# RT1064_Interaction.net
KiCad netlist of a schematic drawn in Altium Designer
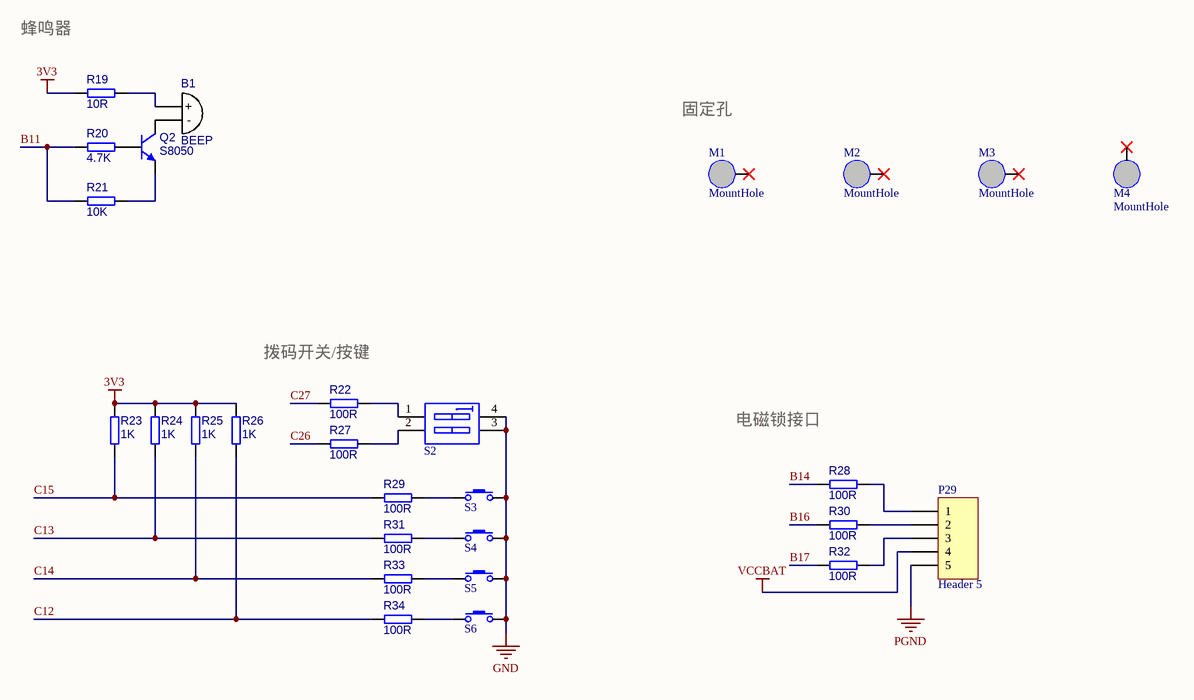
[diagram p0: RT1064_Interaction.SchDoc]

(export (version "E")
  (design (tool "Eeschema 10.0.6"))
  (components
    (comp (ref "B1")
      (value "BEEP")
      (footprint "BEEP 9x5.5mm")
      (description "蜂鸣器")
      (libsource (lib "RT1064_V1主板器件封装集成库") (part "BEEP"))
    )
    (comp (ref "M1")
      (value "MountHole")
      (footprint "M3-MountHole")
      (description "固定孔")
      (libsource (lib "RT1064_V1主板器件封装集成库") (part "MountHole"))
    )
    (comp (ref "M2")
      (value "MountHole")
      (footprint "M3-MountHole")
      (description "固定孔")
      (libsource (lib "RT1064_V1主板器件封装集成库") (part "MountHole"))
    )
    (comp (ref "M3")
      (value "MountHole")
      (footprint "M3-MountHole")
      (description "固定孔")
      (libsource (lib "RT1064_V1主板器件封装集成库") (part "MountHole"))
    )
    (comp (ref "M4")
      (value "MountHole")
      (footprint "M3-MountHole")
      (description "固定孔")
      (libsource (lib "RT1064_V1主板器件封装集成库") (part "MountHole"))
    )
    (comp (ref "P29")
      (value "Header 5")
      (footprint "HDR1X5")
      (description "Header, 5-Pin")
      (fields (field (name "PUBLISHER") "Altium Limited"))
      (libsource (lib "Miscellaneous Connectors") (part "Header 5"))
    )
    (comp (ref "Q2")
      (value "S8050")
      (footprint "SOT-23")
      (description "Discrete NPN Bipolar Transistor")
      (fields (field (name "PARTNUMBER") "S8050") (field (name "PUBLISHER") "Altium Limited"))
      (libsource (lib "RT1064_V1主板器件封装集成库") (part "NPN S8050"))
    )
    (comp (ref "R19")
      (value "10R")
      (footprint "RESC1608[0603]S-L")
      (description "贴片电阻")
      (fields (field (name "POWER") "1/8W") (field (name "TOLERANCE") "±1%"))
      (libsource (lib "RT1064_V1主板器件封装集成库") (part "Res-Chip"))
    )
    (comp (ref "R20")
      (value "4.7K")
      (footprint "RESC1608[0603]S-L")
      (description "贴片电阻")
      (fields (field (name "POWER") "1/8W") (field (name "TOLERANCE") "±1%"))
      (libsource (lib "RT1064_V1主板器件封装集成库") (part "Res-Chip"))
    )
    (comp (ref "R21")
      (value "10K")
      (footprint "RESC1608[0603]S-L")
      (description "贴片电阻")
      (fields (field (name "POWER") "1/8W") (field (name "TOLERANCE") "±1%"))
      (libsource (lib "RT1064_V1主板器件封装集成库") (part "Res-Chip"))
    )
    (comp (ref "R22")
      (value "100R")
      (footprint "RESC1608[0603]S-L")
      (description "贴片电阻")
      (fields (field (name "POWER") "1/8W") (field (name "TOLERANCE") "±1%"))
      (libsource (lib "RT1064_V1主板器件封装集成库") (part "Res-Chip"))
    )
    (comp (ref "R23")
      (value "1K")
      (footprint "RESC1608[0603]S-L")
      (description "贴片电阻")
      (fields (field (name "POWER") "1/8W") (field (name "TOLERANCE") "±1%"))
      (libsource (lib "RT1064_V1主板器件封装集成库") (part "Res-Chip"))
    )
    (comp (ref "R24")
      (value "1K")
      (footprint "RESC1608[0603]S-L")
      (description "贴片电阻")
      (fields (field (name "POWER") "1/8W") (field (name "TOLERANCE") "±1%"))
      (libsource (lib "RT1064_V1主板器件封装集成库") (part "Res-Chip"))
    )
    (comp (ref "R25")
      (value "1K")
      (footprint "RESC1608[0603]S-L")
      (description "贴片电阻")
      (fields (field (name "POWER") "1/8W") (field (name "TOLERANCE") "±1%"))
      (libsource (lib "RT1064_V1主板器件封装集成库") (part "Res-Chip"))
    )
    (comp (ref "R26")
      (value "1K")
      (footprint "RESC1608[0603]S-L")
      (description "贴片电阻")
      (fields (field (name "POWER") "1/8W") (field (name "TOLERANCE") "±1%"))
      (libsource (lib "RT1064_V1主板器件封装集成库") (part "Res-Chip"))
    )
    (comp (ref "R27")
      (value "100R")
      (footprint "RESC1608[0603]S-L")
      (description "贴片电阻")
      (fields (field (name "POWER") "1/8W") (field (name "TOLERANCE") "±1%"))
      (libsource (lib "RT1064_V1主板器件封装集成库") (part "Res-Chip"))
    )
    (comp (ref "R28")
      (value "100R")
      (footprint "RESC1608[0603]S-L")
      (description "贴片电阻")
      (fields (field (name "POWER") "1/8W") (field (name "TOLERANCE") "±1%"))
      (libsource (lib "RT1064_V1主板器件封装集成库") (part "Res-Chip"))
    )
    (comp (ref "R29")
      (value "100R")
      (footprint "RESC1608[0603]S-L")
      (description "贴片电阻")
      (fields (field (name "POWER") "1/8W") (field (name "TOLERANCE") "±1%"))
      (libsource (lib "RT1064_V1主板器件封装集成库") (part "Res-Chip"))
    )
    (comp (ref "R30")
      (value "100R")
      (footprint "RESC1608[0603]S-L")
      (description "贴片电阻")
      (fields (field (name "POWER") "1/8W") (field (name "TOLERANCE") "±1%"))
      (libsource (lib "RT1064_V1主板器件封装集成库") (part "Res-Chip"))
    )
    (comp (ref "R31")
      (value "100R")
      (footprint "RESC1608[0603]S-L")
      (description "贴片电阻")
      (fields (field (name "POWER") "1/8W") (field (name "TOLERANCE") "±1%"))
      (libsource (lib "RT1064_V1主板器件封装集成库") (part "Res-Chip"))
    )
    (comp (ref "R32")
      (value "100R")
      (footprint "RESC1608[0603]S-L")
      (description "贴片电阻")
      (fields (field (name "POWER") "1/8W") (field (name "TOLERANCE") "±1%"))
      (libsource (lib "RT1064_V1主板器件封装集成库") (part "Res-Chip"))
    )
    (comp (ref "R33")
      (value "100R")
      (footprint "RESC1608[0603]S-L")
      (description "贴片电阻")
      (fields (field (name "POWER") "1/8W") (field (name "TOLERANCE") "±1%"))
      (libsource (lib "RT1064_V1主板器件封装集成库") (part "Res-Chip"))
    )
    (comp (ref "R34")
      (value "100R")
      (footprint "RESC1608[0603]S-L")
      (description "贴片电阻")
      (fields (field (name "POWER") "1/8W") (field (name "TOLERANCE") "±1%"))
      (libsource (lib "RT1064_V1主板器件封装集成库") (part "Res-Chip"))
    )
    (comp (ref "S2")
      (value "SW DIP-2")
      (footprint "Code SW-2-DIP-2.54")
      (description "2位拨码开关")
      (fields (field (name "PUBLISHER") "Altium Limited"))
      (libsource (lib "RT1064_V1主板器件封装集成库") (part "Code SW-2"))
    )
    (comp (ref "S3")
      (value "Button")
      (footprint "PTS810-3*4-CurvePin")
      (description "按键")
      (fields (field (name "PUBLISHER") "Altium Limited"))
      (libsource (lib "RT1064_V1主板器件封装集成库") (part "KEY"))
    )
    (comp (ref "S4")
      (value "Button")
      (footprint "PTS810-3*4-CurvePin")
      (description "按键")
      (fields (field (name "PUBLISHER") "Altium Limited"))
      (libsource (lib "RT1064_V1主板器件封装集成库") (part "KEY"))
    )
    (comp (ref "S5")
      (value "Button")
      (footprint "PTS810-3*4-CurvePin")
      (description "按键")
      (fields (field (name "PUBLISHER") "Altium Limited"))
      (libsource (lib "RT1064_V1主板器件封装集成库") (part "KEY"))
    )
    (comp (ref "S6")
      (value "Button")
      (footprint "PTS810-3*4-CurvePin")
      (description "按键")
      (fields (field (name "PUBLISHER") "Altium Limited"))
      (libsource (lib "RT1064_V1主板器件封装集成库") (part "KEY"))
    )
  )
  (nets
    (net (code "1") (name "/B11") (class "Default")
      (node (ref "R20") (pin "2") (pinfunction "2_2") (pintype "passive"))
      (node (ref "R21") (pin "2") (pinfunction "2_2") (pintype "passive"))
    )
    (net (code "2") (name "/B14") (class "Default")
      (node (ref "R28") (pin "2") (pinfunction "2_2") (pintype "passive"))
    )
    (net (code "3") (name "/B16") (class "Default")
      (node (ref "R30") (pin "2") (pinfunction "2_2") (pintype "passive"))
    )
    (net (code "4") (name "/B17") (class "Default")
      (node (ref "R32") (pin "2") (pinfunction "2_2") (pintype "passive"))
    )
    (net (code "5") (name "/C12") (class "Default")
      (node (ref "R26") (pin "2") (pinfunction "2_2") (pintype "passive"))
      (node (ref "R34") (pin "2") (pinfunction "2_2") (pintype "passive"))
    )
    (net (code "6") (name "/C13") (class "Default")
      (node (ref "R24") (pin "2") (pinfunction "2_2") (pintype "passive"))
      (node (ref "R31") (pin "2") (pinfunction "2_2") (pintype "passive"))
    )
    (net (code "7") (name "/C14") (class "Default")
      (node (ref "R25") (pin "2") (pinfunction "2_2") (pintype "passive"))
      (node (ref "R33") (pin "2") (pinfunction "2_2") (pintype "passive"))
    )
    (net (code "8") (name "/C15") (class "Default")
      (node (ref "R23") (pin "2") (pinfunction "2_2") (pintype "passive"))
      (node (ref "R29") (pin "2") (pinfunction "2_2") (pintype "passive"))
    )
    (net (code "9") (name "/C26") (class "Default")
      (node (ref "R27") (pin "2") (pinfunction "2_2") (pintype "passive"))
    )
    (net (code "10") (name "/C27") (class "Default")
      (node (ref "R22") (pin "2") (pinfunction "2_2") (pintype "passive"))
    )
    (net (code "11") (name "3V3") (class "Default")
      (node (ref "R19") (pin "2") (pinfunction "2_2") (pintype "passive"))
      (node (ref "R23") (pin "1") (pinfunction "1_1") (pintype "passive"))
      (node (ref "R24") (pin "1") (pinfunction "1_1") (pintype "passive"))
      (node (ref "R25") (pin "1") (pinfunction "1_1") (pintype "passive"))
      (node (ref "R26") (pin "1") (pinfunction "1_1") (pintype "passive"))
    )
    (net (code "12") (name "GND") (class "Default")
      (node (ref "S2") (pin "3") (pinfunction "B2_3") (pintype "passive"))
      (node (ref "S2") (pin "4") (pinfunction "B1_4") (pintype "passive"))
      (node (ref "S3") (pin "1") (pinfunction "1_1") (pintype "passive"))
      (node (ref "S4") (pin "1") (pinfunction "1_1") (pintype "passive"))
      (node (ref "S5") (pin "1") (pinfunction "1_1") (pintype "passive"))
      (node (ref "S6") (pin "1") (pinfunction "1_1") (pintype "passive"))
    )
    (net (code "13") (name "Net-(B1-+)") (class "Default")
      (node (ref "B1") (pin "1") (pinfunction "+_1") (pintype "passive"))
      (node (ref "R19") (pin "1") (pinfunction "1_1") (pintype "passive"))
    )
    (net (code "14") (name "Net-(B1--)") (class "Default")
      (node (ref "B1") (pin "2") (pinfunction "-_2") (pintype "passive"))
      (node (ref "Q2") (pin "3") (pinfunction "C_3") (pintype "passive"))
    )
    (net (code "15") (name "Net-(P29-Pad1)") (class "Default")
      (node (ref "P29") (pin "1") (pinfunction "1_1") (pintype "passive"))
      (node (ref "R28") (pin "1") (pinfunction "1_1") (pintype "passive"))
    )
    (net (code "16") (name "Net-(P29-Pad2)") (class "Default")
      (node (ref "P29") (pin "2") (pinfunction "2_2") (pintype "passive"))
      (node (ref "R30") (pin "1") (pinfunction "1_1") (pintype "passive"))
    )
    (net (code "17") (name "Net-(P29-Pad3)") (class "Default")
      (node (ref "P29") (pin "3") (pinfunction "3_3") (pintype "passive"))
      (node (ref "R32") (pin "1") (pinfunction "1_1") (pintype "passive"))
    )
    (net (code "18") (name "Net-(Q2-B)") (class "Default")
      (node (ref "Q2") (pin "1") (pinfunction "B_1") (pintype "passive"))
      (node (ref "R20") (pin "1") (pinfunction "1_1") (pintype "passive"))
    )
    (net (code "19") (name "Net-(Q2-E)") (class "Default")
      (node (ref "Q2") (pin "2") (pinfunction "E_2") (pintype "passive"))
      (node (ref "R21") (pin "1") (pinfunction "1_1") (pintype "passive"))
    )
    (net (code "20") (name "Net-(R29-Pad1)") (class "Default")
      (node (ref "R29") (pin "1") (pinfunction "1_1") (pintype "passive"))
      (node (ref "S3") (pin "2") (pinfunction "2_2") (pintype "passive"))
    )
    (net (code "21") (name "Net-(R31-Pad1)") (class "Default")
      (node (ref "R31") (pin "1") (pinfunction "1_1") (pintype "passive"))
      (node (ref "S4") (pin "2") (pinfunction "2_2") (pintype "passive"))
    )
    (net (code "22") (name "Net-(R33-Pad1)") (class "Default")
      (node (ref "R33") (pin "1") (pinfunction "1_1") (pintype "passive"))
      (node (ref "S5") (pin "2") (pinfunction "2_2") (pintype "passive"))
    )
    (net (code "23") (name "Net-(R34-Pad1)") (class "Default")
      (node (ref "R34") (pin "1") (pinfunction "1_1") (pintype "passive"))
      (node (ref "S6") (pin "2") (pinfunction "2_2") (pintype "passive"))
    )
    (net (code "24") (name "Net-(S2-A1)") (class "Default")
      (node (ref "R22") (pin "1") (pinfunction "1_1") (pintype "passive"))
      (node (ref "S2") (pin "1") (pinfunction "A1_1") (pintype "passive"))
    )
    (net (code "25") (name "Net-(S2-A2)") (class "Default")
      (node (ref "R27") (pin "1") (pinfunction "1_1") (pintype "passive"))
      (node (ref "S2") (pin "2") (pinfunction "A2_2") (pintype "passive"))
    )
    (net (code "26") (name "PGND") (class "Default")
      (node (ref "P29") (pin "5") (pinfunction "5_5") (pintype "passive"))
    )
    (net (code "27") (name "VCCBAT") (class "Default")
      (node (ref "P29") (pin "4") (pinfunction "4_4") (pintype "passive"))
    )
    (net (code "28") (name "unconnected-(M1-Pad1)") (class "Default")
      (node (ref "M1") (pin "1") (pinfunction "1_1") (pintype "passive+no_connect"))
    )
    (net (code "29") (name "unconnected-(M2-Pad1)") (class "Default")
      (node (ref "M2") (pin "1") (pinfunction "1_1") (pintype "passive+no_connect"))
    )
    (net (code "30") (name "unconnected-(M3-Pad1)") (class "Default")
      (node (ref "M3") (pin "1") (pinfunction "1_1") (pintype "passive+no_connect"))
    )
    (net (code "31") (name "unconnected-(M4-Pad1)") (class "Default")
      (node (ref "M4") (pin "1") (pinfunction "1_1") (pintype "passive+no_connect"))
    )
  )
)
